# Gluon.net
KiCad netlist of a schematic drawn in Altium Designer
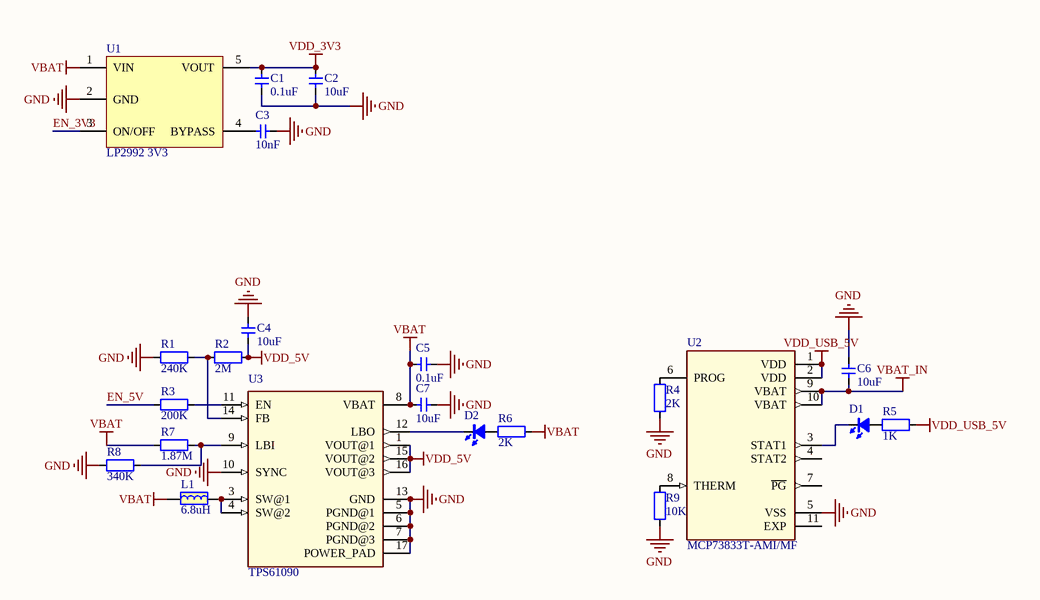
[diagram p0: Gluon.SchDoc]

(export (version "E")
  (design (tool "Eeschema 10.0.6"))
  (components
    (comp (ref "C1")
      (value "0.1uF")
      (footprint "CAP_0402")
      (description "Capacitor")
      (libsource (lib "MyPcbLib") (part "电容-0402"))
    )
    (comp (ref "C2")
      (value "10uF")
      (footprint "0603-CAP")
      (description "Capacitor")
      (libsource (lib "MyPcbLib") (part "电容-0603"))
    )
    (comp (ref "C3")
      (value "10nF")
      (footprint "CAP_0402")
      (description "Capacitor")
      (libsource (lib "MyPcbLib") (part "电容-0402"))
    )
    (comp (ref "C4")
      (value "10uF")
      (footprint "0603-CAP")
      (description "Capacitor")
      (libsource (lib "MyPcbLib") (part "电容-0603"))
    )
    (comp (ref "C5")
      (value "0.1uF")
      (footprint "CAP_0402")
      (description "Capacitor")
      (libsource (lib "MyPcbLib") (part "电容-0402"))
    )
    (comp (ref "C6")
      (value "10uF")
      (footprint "0603-CAP")
      (description "Capacitor")
      (libsource (lib "MyPcbLib") (part "电容-0603"))
    )
    (comp (ref "C7")
      (value "10uF")
      (footprint "0603-CAP")
      (description "Capacitor")
      (libsource (lib "MyPcbLib") (part "电容-0603"))
    )
    (comp (ref "D1")
      (value "color?")
      (footprint "LED_0402_RED")
      (description "LED")
      (libsource (lib "KitSprout") (part "LED_0402"))
    )
    (comp (ref "D2")
      (value "~")
      (footprint "LED_0402_RED")
      (description "LED")
      (libsource (lib "KitSprout") (part "LED_0402"))
    )
    (comp (ref "L1")
      (value "6.8uH")
      (footprint "2520-L")
      (description "磁珠")
      (libsource (lib "MyPcbLib") (part "电感-2520"))
    )
    (comp (ref "R1")
      (value "240K")
      (footprint "RES_0402")
      (description "Resistor")
      (libsource (lib "MyPcbLib") (part "电阻-0402"))
    )
    (comp (ref "R2")
      (value "2M")
      (footprint "RES_0402")
      (description "Resistor")
      (libsource (lib "MyPcbLib") (part "电阻-0402"))
    )
    (comp (ref "R3")
      (value "200K")
      (footprint "RES_0402")
      (description "Resistor")
      (libsource (lib "MyPcbLib") (part "电阻-0402"))
    )
    (comp (ref "R4")
      (value "2K")
      (footprint "RES_0402")
      (description "Resistor")
      (libsource (lib "") (part "电阻-0402_2"))
    )
    (comp (ref "R5")
      (value "1K")
      (footprint "RES_0402")
      (description "Resistor")
      (libsource (lib "") (part "电阻-0402_1"))
    )
    (comp (ref "R6")
      (value "2K")
      (footprint "RES_0402")
      (description "Resistor")
      (libsource (lib "MyPcbLib") (part "电阻-0402"))
    )
    (comp (ref "R7")
      (value "1.87M")
      (footprint "RES_0402")
      (description "Resistor")
      (libsource (lib "MyPcbLib") (part "电阻-0402"))
    )
    (comp (ref "R8")
      (value "340K")
      (footprint "RES_0402")
      (description "Resistor")
      (libsource (lib "MyPcbLib") (part "电阻-0402"))
    )
    (comp (ref "R9")
      (value "10K")
      (footprint "RES_0402")
      (description "Resistor")
      (libsource (lib "") (part "电阻-0402_2"))
    )
    (comp (ref "U1")
      (value "LP2992 3V3")
      (footprint "SOT23-5")
      (description "LDO")
      (libsource (lib "MyPcbLib") (part "LP2992"))
    )
    (comp (ref "U2")
      (value "MCP73833T-AMI/MF")
      (footprint "QFN-10")
      (description "Linear Charge Management Controller Li-Ion/Li-Pol 1mA 4.2V/4.35V/4.4V/4.5V 10-Pin DFN EP T/R")
      (fields (field (name "MF") "Microchip"))
      (libsource (lib "mLib") (part "MCP73833T"))
    )
    (comp (ref "U3")
      (value "TPS61090")
      (footprint "QFN-16")
      (fields (field (name "MF") "Texas Instruments"))
      (libsource (lib "MyPcbLib") (part "TPS61090"))
    )
  )
  (nets
    (net (code "1") (name "/EN_3V3") (class "Default")
      (node (ref "U1") (pin "3") (pinfunction "ON/OFF_3") (pintype "passive"))
    )
    (net (code "2") (name "/EN_5V") (class "Default")
      (node (ref "R3") (pin "1") (pinfunction "1_1") (pintype "passive"))
    )
    (net (code "3") (name "GND") (class "Default")
      (node (ref "C1") (pin "1") (pinfunction "1_1") (pintype "passive"))
      (node (ref "C2") (pin "1") (pinfunction "1_1") (pintype "passive"))
      (node (ref "C3") (pin "1") (pinfunction "1_1") (pintype "passive"))
      (node (ref "C4") (pin "2") (pinfunction "2_2") (pintype "passive"))
      (node (ref "C5") (pin "2") (pinfunction "2_2") (pintype "passive"))
      (node (ref "C6") (pin "2") (pinfunction "2_2") (pintype "passive"))
      (node (ref "C7") (pin "1") (pinfunction "1_1") (pintype "passive"))
      (node (ref "R1") (pin "1") (pinfunction "1_1") (pintype "passive"))
      (node (ref "R4") (pin "1") (pinfunction "1_1") (pintype "passive"))
      (node (ref "R8") (pin "1") (pinfunction "1_1") (pintype "passive"))
      (node (ref "R9") (pin "1") (pinfunction "1_1") (pintype "passive"))
      (node (ref "U1") (pin "2") (pinfunction "GND_2") (pintype "passive"))
      (node (ref "U2") (pin "5") (pinfunction "VSS_5") (pintype "power_in"))
      (node (ref "U3") (pin "10") (pinfunction "SYNC_10") (pintype "input"))
      (node (ref "U3") (pin "13") (pinfunction "GND_13") (pintype "power_in"))
      (node (ref "U3") (pin "17") (pinfunction "POWER_PAD_17") (pintype "power_in"))
      (node (ref "U3") (pin "5") (pinfunction "PGND@1_5") (pintype "power_in"))
      (node (ref "U3") (pin "6") (pinfunction "PGND@2_6") (pintype "power_in"))
      (node (ref "U3") (pin "7") (pinfunction "PGND@3_7") (pintype "power_in"))
    )
    (net (code "4") (name "Net-(D1-A)") (class "Default")
      (node (ref "D1") (pin "1") (pinfunction "A_1") (pintype "passive"))
      (node (ref "R5") (pin "2") (pinfunction "2_2") (pintype "passive"))
    )
    (net (code "5") (name "Net-(D1-K)") (class "Default")
      (node (ref "D1") (pin "2") (pinfunction "K_2") (pintype "passive"))
      (node (ref "U2") (pin "3") (pinfunction "STAT1_3") (pintype "output"))
    )
    (net (code "6") (name "Net-(D2-A)") (class "Default")
      (node (ref "D2") (pin "1") (pinfunction "A_1") (pintype "passive"))
      (node (ref "R6") (pin "1") (pinfunction "1_1") (pintype "passive"))
    )
    (net (code "7") (name "Net-(D2-K)") (class "Default")
      (node (ref "D2") (pin "2") (pinfunction "K_2") (pintype "passive"))
      (node (ref "U3") (pin "12") (pinfunction "LBO_12") (pintype "output"))
    )
    (net (code "8") (name "Net-(U1-BYPASS)") (class "Default")
      (node (ref "C3") (pin "2") (pinfunction "2_2") (pintype "passive"))
      (node (ref "U1") (pin "4") (pinfunction "BYPASS_4") (pintype "passive"))
    )
    (net (code "9") (name "Net-(U2-PROG)") (class "Default")
      (node (ref "R4") (pin "2") (pinfunction "2_2") (pintype "passive"))
      (node (ref "U2") (pin "6") (pinfunction "PROG_6") (pintype "passive"))
    )
    (net (code "10") (name "Net-(U2-THERM)") (class "Default")
      (node (ref "R9") (pin "2") (pinfunction "2_2") (pintype "passive"))
      (node (ref "U2") (pin "8") (pinfunction "THERM_8") (pintype "input"))
    )
    (net (code "11") (name "Net-(U3-EN)") (class "Default")
      (node (ref "R3") (pin "2") (pinfunction "2_2") (pintype "passive"))
      (node (ref "U3") (pin "11") (pinfunction "EN_11") (pintype "input"))
    )
    (net (code "12") (name "Net-(U3-FB)") (class "Default")
      (node (ref "R1") (pin "2") (pinfunction "2_2") (pintype "passive"))
      (node (ref "R2") (pin "1") (pinfunction "1_1") (pintype "passive"))
      (node (ref "U3") (pin "14") (pinfunction "FB_14") (pintype "input"))
    )
    (net (code "13") (name "Net-(U3-LBI)") (class "Default")
      (node (ref "R7") (pin "2") (pinfunction "2_2") (pintype "passive"))
      (node (ref "R8") (pin "2") (pinfunction "2_2") (pintype "passive"))
      (node (ref "U3") (pin "9") (pinfunction "LBI_9") (pintype "input"))
    )
    (net (code "14") (name "Net-(U3-SW@1)") (class "Default")
      (node (ref "L1") (pin "2") (pinfunction "2_2") (pintype "passive"))
      (node (ref "U3") (pin "3") (pinfunction "SW@1_3") (pintype "input"))
      (node (ref "U3") (pin "4") (pinfunction "SW@2_4") (pintype "input"))
    )
    (net (code "15") (name "VBAT") (class "Default")
      (node (ref "C5") (pin "1") (pinfunction "1_1") (pintype "passive"))
      (node (ref "C7") (pin "2") (pinfunction "2_2") (pintype "passive"))
      (node (ref "L1") (pin "1") (pintype "passive"))
      (node (ref "R6") (pin "2") (pinfunction "2_2") (pintype "passive"))
      (node (ref "R7") (pin "1") (pinfunction "1_1") (pintype "passive"))
      (node (ref "U1") (pin "1") (pinfunction "VIN_1") (pintype "passive"))
      (node (ref "U3") (pin "8") (pinfunction "VBAT_8") (pintype "power_in"))
    )
    (net (code "16") (name "VBAT_IN") (class "Default")
      (node (ref "C6") (pin "1") (pinfunction "1_1") (pintype "passive"))
      (node (ref "U2") (pin "10") (pinfunction "VBAT_10") (pintype "output"))
      (node (ref "U2") (pin "9") (pinfunction "VBAT_9") (pintype "output"))
    )
    (net (code "17") (name "VDD_3V3") (class "Default")
      (node (ref "C1") (pin "2") (pinfunction "2_2") (pintype "passive"))
      (node (ref "C2") (pin "2") (pinfunction "2_2") (pintype "passive"))
      (node (ref "U1") (pin "5") (pinfunction "VOUT_5") (pintype "passive"))
    )
    (net (code "18") (name "VDD_5V") (class "Default")
      (node (ref "C4") (pin "1") (pinfunction "1_1") (pintype "passive"))
      (node (ref "R2") (pin "2") (pinfunction "2_2") (pintype "passive"))
      (node (ref "U3") (pin "1") (pinfunction "VOUT@1_1") (pintype "output"))
      (node (ref "U3") (pin "15") (pinfunction "VOUT@2_15") (pintype "output"))
      (node (ref "U3") (pin "16") (pinfunction "VOUT@3_16") (pintype "output"))
    )
    (net (code "19") (name "VDD_USB_5V") (class "Default")
      (node (ref "R5") (pin "1") (pinfunction "1_1") (pintype "passive"))
      (node (ref "U2") (pin "1") (pinfunction "VDD_1") (pintype "power_in"))
      (node (ref "U2") (pin "2") (pinfunction "VDD_2") (pintype "power_in"))
    )
    (net (code "20") (name "unconnected-(U2-EXP-Pad11)") (class "Default")
      (node (ref "U2") (pin "11") (pinfunction "EXP_11") (pintype "passive"))
    )
    (net (code "21") (name "unconnected-(U2-STAT2-Pad4)") (class "Default")
      (node (ref "U2") (pin "4") (pinfunction "STAT2_4") (pintype "output"))
    )
    (net (code "22") (name "unconnected-(U2-~{PG}-Pad7)") (class "Default")
      (node (ref "U2") (pin "7") (pinfunction "~{PG}_7") (pintype "output"))
    )
  )
)
